# roller-shutter.net
KiCad netlist of a schematic drawn in EAGLE
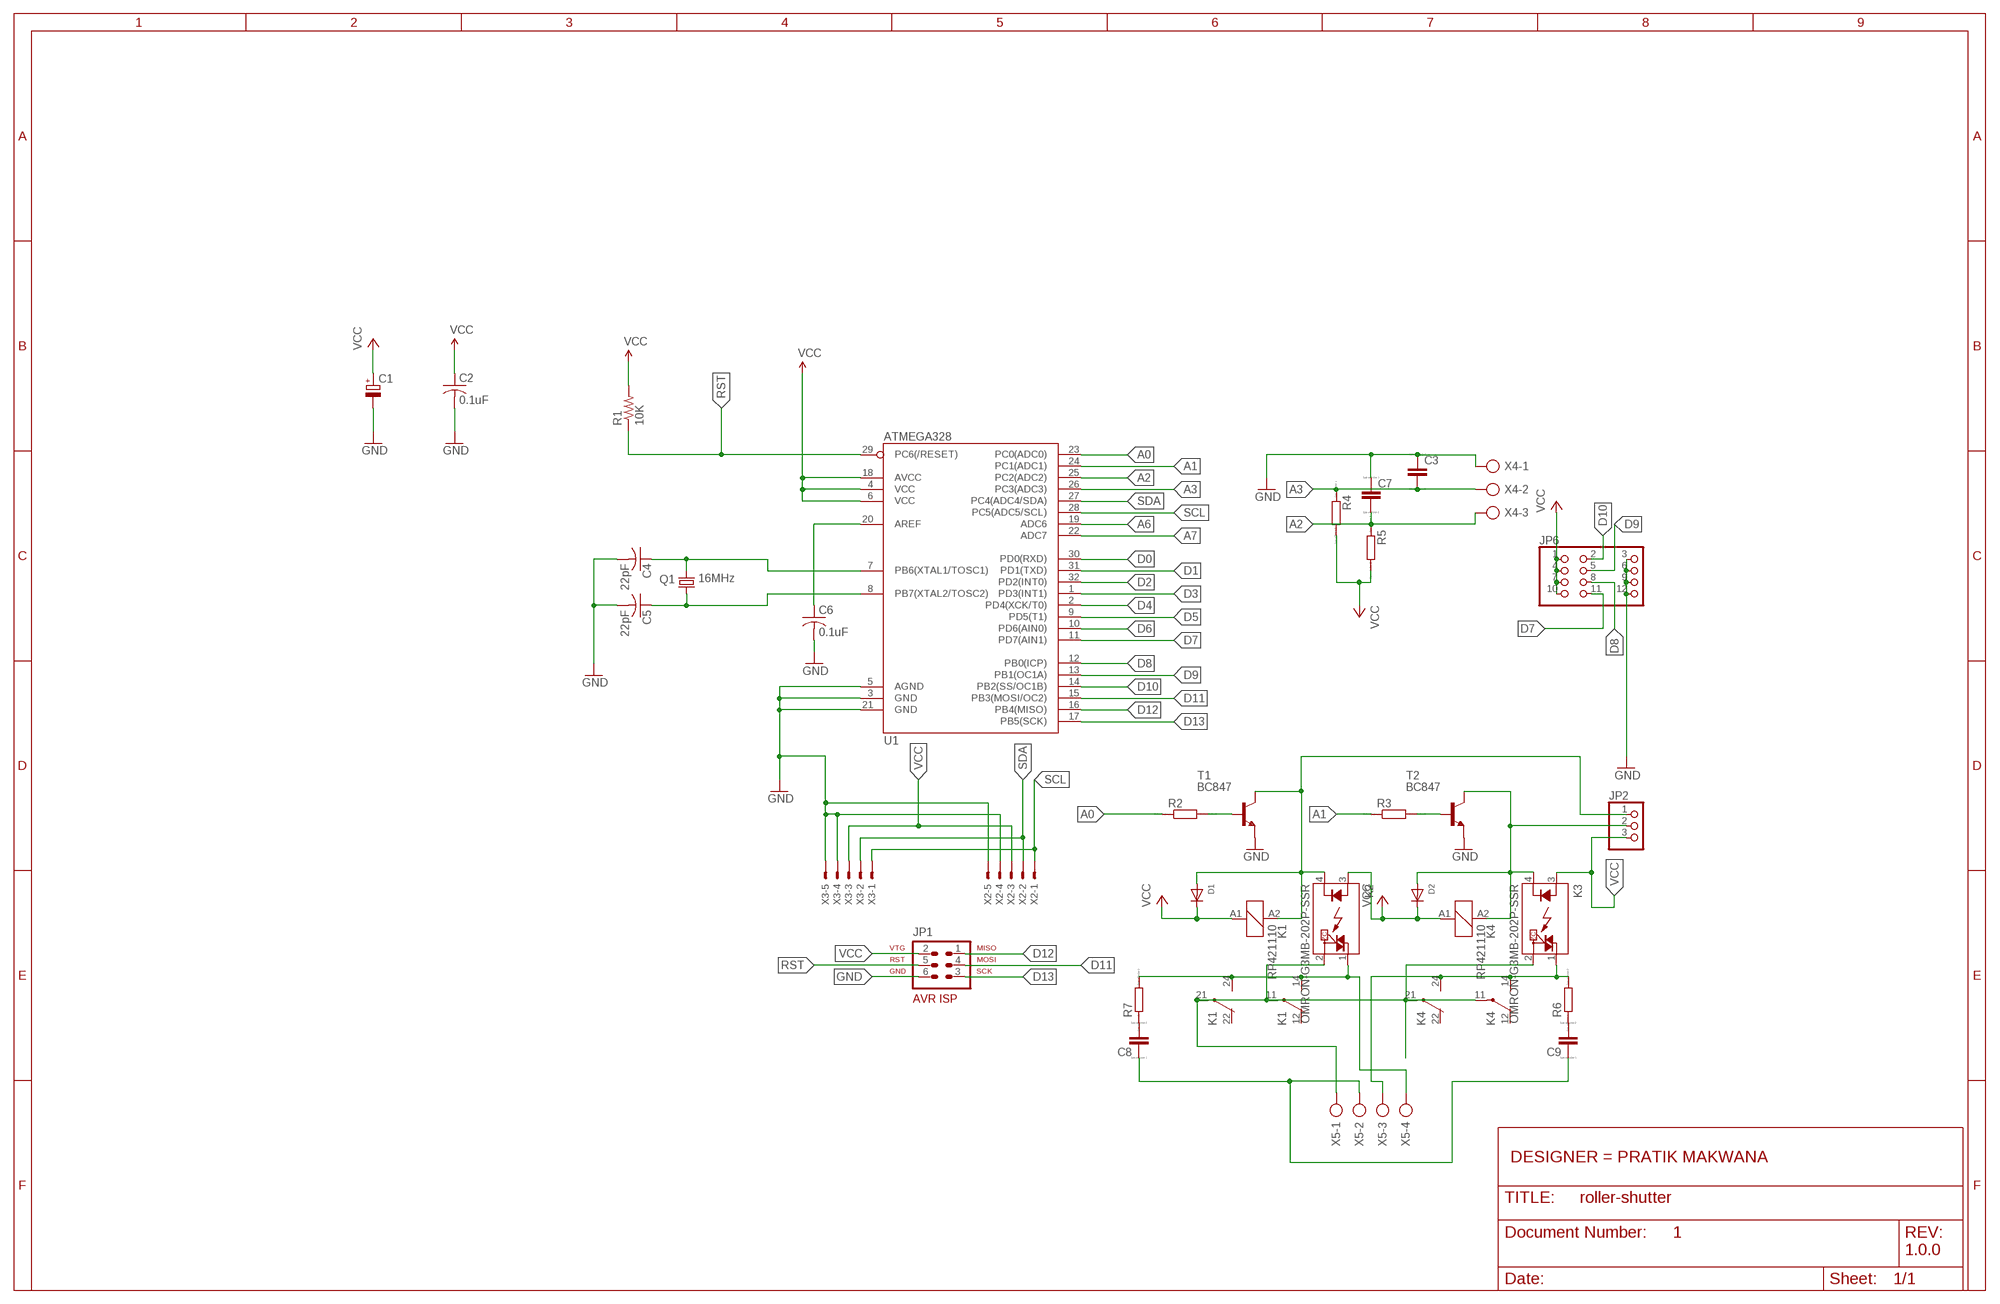
[diagram p0: schematic, sheet 1]

(export (version "E")
  (design (tool "Eeschema 10.0.6"))
  (components
    (comp (ref "C1")
      (value "CPOL-EUSANYO_SMD_C6")
      (footprint "eagle-import:SANYO-OSCON_SMD_C6")
      (libsource (lib "eagle-import") (part "CPOL-EUSANYO_SMD_C6"))
    )
    (comp (ref "C2")
      (value "0.1uF")
      (footprint "eagle-import:C0805")
      (libsource (lib "eagle-import") (part "C-USC0805"))
    )
    (comp (ref "C3") (value "C") (footprint "eagle-import:C0805") (libsource (lib "eagle-import") (part "C")))
    (comp (ref "C4")
      (value "22pF")
      (footprint "eagle-import:C1206")
      (libsource (lib "eagle-import") (part "C-USC1206"))
    )
    (comp (ref "C5")
      (value "22pF")
      (footprint "eagle-import:C1206")
      (libsource (lib "eagle-import") (part "C-USC1206"))
    )
    (comp (ref "C6")
      (value "0.1uF")
      (footprint "eagle-import:C0805")
      (libsource (lib "eagle-import") (part "C-USC0805"))
    )
    (comp (ref "C7") (value "C") (footprint "eagle-import:C0805") (libsource (lib "eagle-import") (part "C")))
    (comp (ref "C8")
      (value "CC1812")
      (footprint "eagle-import:C1812")
      (libsource (lib "eagle-import") (part "CC1812"))
    )
    (comp (ref "C9")
      (value "CC1812")
      (footprint "eagle-import:C1812")
      (libsource (lib "eagle-import") (part "CC1812"))
    )
    (comp (ref "D1")
      (value "DIODE_SOD-123FL")
      (footprint "eagle-import:SOD-123FL")
      (libsource (lib "eagle-import") (part "DIODE_SOD-123FL"))
    )
    (comp (ref "D2")
      (value "DIODE_SOD-123FL")
      (footprint "eagle-import:SOD-123FL")
      (libsource (lib "eagle-import") (part "DIODE_SOD-123FL"))
    )
    (comp (ref "JP1")
      (value "AVR-ISP-6")
      (footprint "eagle-import:AVR-ISP-6")
      (libsource (lib "eagle-import") (part "AVR-ISP-6"))
    )
    (comp (ref "JP2")
      (value "PINHD-1X3")
      (footprint "eagle-import:1X03")
      (libsource (lib "eagle-import") (part "PINHD-1X3"))
    )
    (comp (ref "JP6")
      (value "PINHD-3X4")
      (footprint "eagle-import:3X04")
      (libsource (lib "eagle-import") (part "PINHD-3X4"))
    )
    (comp (ref "K1")
      (value "RP421110")
      (footprint "eagle-import:RP420")
      (fields (field (name "MF") "TYCO ELECTRONICS"))
      (libsource (lib "eagle-import") (part "RP42?1110"))
    )
    (comp (ref "K2")
      (value "OMRON-G3MB-202P-SSR")
      (footprint "eagle-import:OMRON-G3MB-202P-SSR")
      (libsource (lib "eagle-import") (part "OMRON-G3MB-202P-SSR"))
    )
    (comp (ref "K3")
      (value "OMRON-G3MB-202P-SSR")
      (footprint "eagle-import:OMRON-G3MB-202P-SSR")
      (libsource (lib "eagle-import") (part "OMRON-G3MB-202P-SSR"))
    )
    (comp (ref "K4")
      (value "RP421110")
      (footprint "eagle-import:RP420")
      (fields (field (name "MF") "TYCO ELECTRONICS"))
      (libsource (lib "eagle-import") (part "RP42?1110"))
    )
    (comp (ref "Q1")
      (value "16MHz")
      (footprint "eagle-import:HC49_S")
      (libsource (lib "eagle-import") (part "CRYTALHC49S"))
    )
    (comp (ref "R1")
      (value "10K")
      (footprint "eagle-import:R1206")
      (libsource (lib "eagle-import") (part "R-US_R1206"))
    )
    (comp (ref "R2")
      (value "RR1206")
      (footprint "eagle-import:R1206")
      (libsource (lib "eagle-import") (part "RR1206"))
    )
    (comp (ref "R3")
      (value "RR1206")
      (footprint "eagle-import:R1206")
      (libsource (lib "eagle-import") (part "RR1206"))
    )
    (comp (ref "R4")
      (value "RR1206")
      (footprint "eagle-import:R1206")
      (libsource (lib "eagle-import") (part "RR1206"))
    )
    (comp (ref "R5")
      (value "RR1206")
      (footprint "eagle-import:R1206")
      (libsource (lib "eagle-import") (part "RR1206"))
    )
    (comp (ref "R6")
      (value "RR2512")
      (footprint "eagle-import:R2512")
      (libsource (lib "eagle-import") (part "RR2512"))
    )
    (comp (ref "R7")
      (value "RR2512")
      (footprint "eagle-import:R2512")
      (libsource (lib "eagle-import") (part "RR2512"))
    )
    (comp (ref "T1")
      (value "BC847")
      (footprint "eagle-import:SOT23")
      (libsource (lib "eagle-import") (part "BC847"))
    )
    (comp (ref "T2")
      (value "BC847")
      (footprint "eagle-import:SOT23")
      (libsource (lib "eagle-import") (part "BC847"))
    )
    (comp (ref "U1")
      (value "ATMEGA328")
      (footprint "eagle-import:TQFP32-08")
      (libsource (lib "eagle-import") (part "ATMEGA328"))
    )
    (comp (ref "X2")
      (value "JST-XH-05-PIN-LONG-PAD")
      (footprint "eagle-import:JST-XH-05-PACKAGE-LONG-PAD")
      (libsource (lib "eagle-import") (part "JST-XH-05-PIN-LONG-PAD"))
    )
    (comp (ref "X3")
      (value "JST-XH-05-PIN-LONG-PAD")
      (footprint "eagle-import:JST-XH-05-PACKAGE-LONG-PAD")
      (libsource (lib "eagle-import") (part "JST-XH-05-PIN-LONG-PAD"))
    )
    (comp (ref "X4")
      (value "AK500/3")
      (footprint "eagle-import:AK500_3")
      (libsource (lib "eagle-import") (part "AK500/3"))
    )
    (comp (ref "X5")
      (value "AK500/4")
      (footprint "eagle-import:AK500_4")
      (libsource (lib "eagle-import") (part "AK500/4"))
    )
  )
  (nets
    (net (code "1") (name "A0") (class "Default")
      (node (ref "R2") (pin "1") (pinfunction "1_1") (pintype "passive"))
      (node (ref "U1") (pin "23") (pinfunction "PC0(ADC0)_23") (pintype "bidirectional"))
    )
    (net (code "2") (name "A1") (class "Default")
      (node (ref "R3") (pin "1") (pinfunction "1_1") (pintype "passive"))
      (node (ref "U1") (pin "24") (pinfunction "PC1(ADC1)_24") (pintype "bidirectional"))
    )
    (net (code "3") (name "A2") (class "Default")
      (node (ref "C7") (pin "2") (pinfunction "2_2") (pintype "passive"))
      (node (ref "R5") (pin "1") (pinfunction "1_1") (pintype "passive"))
      (node (ref "U1") (pin "25") (pinfunction "PC2(ADC2)_25") (pintype "bidirectional"))
      (node (ref "X4") (pin "3") (pinfunction "KL_3") (pintype "passive"))
    )
    (net (code "4") (name "A3") (class "Default")
      (node (ref "C3") (pin "2") (pinfunction "2_2") (pintype "passive"))
      (node (ref "R4") (pin "1") (pinfunction "1_1") (pintype "passive"))
      (node (ref "U1") (pin "26") (pinfunction "PC3(ADC3)_26") (pintype "bidirectional"))
      (node (ref "X4") (pin "2") (pinfunction "KL_2") (pintype "passive"))
    )
    (net (code "5") (name "A6") (class "Default")
      (node (ref "U1") (pin "19") (pinfunction "ADC6_19") (pintype "bidirectional"))
    )
    (net (code "6") (name "A7") (class "Default")
      (node (ref "U1") (pin "22") (pinfunction "ADC7_22") (pintype "bidirectional"))
    )
    (net (code "7") (name "D0") (class "Default")
      (node (ref "U1") (pin "30") (pinfunction "PD0(RXD)_30") (pintype "bidirectional"))
    )
    (net (code "8") (name "D1") (class "Default")
      (node (ref "U1") (pin "31") (pinfunction "PD1(TXD)_31") (pintype "bidirectional"))
    )
    (net (code "9") (name "D2") (class "Default")
      (node (ref "U1") (pin "32") (pinfunction "PD2(INT0)_32") (pintype "bidirectional"))
    )
    (net (code "10") (name "D3") (class "Default")
      (node (ref "U1") (pin "1") (pinfunction "PD3(INT1)_1") (pintype "bidirectional"))
    )
    (net (code "11") (name "D4") (class "Default")
      (node (ref "U1") (pin "2") (pinfunction "PD4(XCK/T0)_2") (pintype "bidirectional"))
    )
    (net (code "12") (name "D5") (class "Default")
      (node (ref "U1") (pin "9") (pinfunction "PD5(T1)_9") (pintype "bidirectional"))
    )
    (net (code "13") (name "D6") (class "Default")
      (node (ref "U1") (pin "10") (pinfunction "PD6(AIN0)_10") (pintype "bidirectional"))
    )
    (net (code "14") (name "D7") (class "Default")
      (node (ref "JP6") (pin "11") (pinfunction "11_11") (pintype "passive"))
      (node (ref "U1") (pin "11") (pinfunction "PD7(AIN1)_11") (pintype "bidirectional"))
    )
    (net (code "15") (name "D8") (class "Default")
      (node (ref "JP6") (pin "8") (pinfunction "8_8") (pintype "passive"))
      (node (ref "U1") (pin "12") (pinfunction "PB0(ICP)_12") (pintype "bidirectional"))
    )
    (net (code "16") (name "D9") (class "Default")
      (node (ref "JP6") (pin "5") (pinfunction "5_5") (pintype "passive"))
      (node (ref "U1") (pin "13") (pinfunction "PB1(OC1A)_13") (pintype "bidirectional"))
    )
    (net (code "17") (name "D10") (class "Default")
      (node (ref "JP6") (pin "2") (pinfunction "2_2") (pintype "passive"))
      (node (ref "U1") (pin "14") (pinfunction "PB2(SS/OC1B)_14") (pintype "bidirectional"))
    )
    (net (code "18") (name "D11") (class "Default")
      (node (ref "JP1") (pin "4") (pinfunction "4_4") (pintype "passive"))
      (node (ref "U1") (pin "15") (pinfunction "PB3(MOSI/OC2)_15") (pintype "bidirectional"))
    )
    (net (code "19") (name "D12") (class "Default")
      (node (ref "JP1") (pin "1") (pinfunction "1_1") (pintype "passive"))
      (node (ref "U1") (pin "16") (pinfunction "PB4(MISO)_16") (pintype "bidirectional"))
    )
    (net (code "20") (name "D13") (class "Default")
      (node (ref "JP1") (pin "3") (pinfunction "3_3") (pintype "passive"))
      (node (ref "U1") (pin "17") (pinfunction "PB5(SCK)_17") (pintype "bidirectional"))
    )
    (net (code "21") (name "GND") (class "Default")
      (node (ref "C1") (pin "-") (pinfunction "-_-") (pintype "passive"))
      (node (ref "C2") (pin "2") (pinfunction "2_2") (pintype "passive"))
      (node (ref "C3") (pin "1") (pinfunction "1_1") (pintype "passive"))
      (node (ref "C4") (pin "2") (pinfunction "2_2") (pintype "passive"))
      (node (ref "C5") (pin "2") (pinfunction "2_2") (pintype "passive"))
      (node (ref "C6") (pin "2") (pinfunction "2_2") (pintype "passive"))
      (node (ref "C7") (pin "1") (pinfunction "1_1") (pintype "passive"))
      (node (ref "JP1") (pin "6") (pinfunction "6_6") (pintype "passive"))
      (node (ref "JP6") (pin "12") (pinfunction "12_12") (pintype "passive"))
      (node (ref "JP6") (pin "3") (pinfunction "3_3") (pintype "passive"))
      (node (ref "JP6") (pin "6") (pinfunction "6_6") (pintype "passive"))
      (node (ref "JP6") (pin "9") (pinfunction "9_9") (pintype "passive"))
      (node (ref "T1") (pin "2") (pinfunction "E_2") (pintype "passive"))
      (node (ref "T2") (pin "2") (pinfunction "E_2") (pintype "passive"))
      (node (ref "U1") (pin "21") (pinfunction "GND_21") (pintype "bidirectional"))
      (node (ref "U1") (pin "3") (pinfunction "GND_3") (pintype "bidirectional"))
      (node (ref "U1") (pin "5") (pinfunction "AGND_5") (pintype "bidirectional"))
      (node (ref "X2") (pin "4") (pinfunction "S_4") (pintype "passive"))
      (node (ref "X2") (pin "5") (pinfunction "S_5") (pintype "passive"))
      (node (ref "X3") (pin "4") (pinfunction "S_4") (pintype "passive"))
      (node (ref "X3") (pin "5") (pinfunction "S_5") (pintype "passive"))
      (node (ref "X4") (pin "1") (pinfunction "KL_1") (pintype "passive"))
    )
    (net (code "22") (name "Net-(C8-Pad2)") (class "Default")
      (node (ref "C8") (pin "2") (pinfunction "2_2") (pintype "passive"))
      (node (ref "R7") (pin "1") (pinfunction "1_1") (pintype "passive"))
    )
    (net (code "23") (name "Net-(C9-Pad2)") (class "Default")
      (node (ref "C9") (pin "2") (pinfunction "2_2") (pintype "passive"))
      (node (ref "R6") (pin "1") (pinfunction "1_1") (pintype "passive"))
    )
    (net (code "24") (name "Net-(K1A-1)") (class "Default")
      (node (ref "D1") (pin "A") (pinfunction "A_A") (pintype "passive"))
      (node (ref "JP2") (pin "1") (pinfunction "1_1") (pintype "passive"))
      (node (ref "K1") (pin "A2") (pinfunction "1_A2") (pintype "passive"))
      (node (ref "K2") (pin "4") (pinfunction "K_4") (pintype "passive"))
      (node (ref "T1") (pin "3") (pinfunction "C_3") (pintype "passive"))
    )
    (net (code "25") (name "Net-(K1B-P)") (class "Default")
      (node (ref "K1") (pin "11") (pinfunction "P_11") (pintype "passive"))
      (node (ref "K1") (pin "21") (pinfunction "P_21") (pintype "passive"))
      (node (ref "K2") (pin "2") (pinfunction "DS2_2") (pintype "passive"))
      (node (ref "K3") (pin "2") (pinfunction "DS2_2") (pintype "passive"))
      (node (ref "K4") (pin "11") (pinfunction "P_11") (pintype "passive"))
      (node (ref "K4") (pin "21") (pinfunction "P_21") (pintype "passive"))
      (node (ref "X5") (pin "1") (pinfunction "KL_1") (pintype "passive"))
    )
    (net (code "26") (name "Net-(K1B-S)") (class "Default")
      (node (ref "K1") (pin "14") (pinfunction "S_14") (pintype "passive"))
      (node (ref "K1") (pin "24") (pinfunction "S_24") (pintype "passive"))
      (node (ref "K2") (pin "1") (pinfunction "DS1_1") (pintype "passive"))
      (node (ref "R7") (pin "2") (pinfunction "2_2") (pintype "passive"))
      (node (ref "X5") (pin "4") (pinfunction "KL_4") (pintype "passive"))
    )
    (net (code "27") (name "Net-(K3-DS1)") (class "Default")
      (node (ref "K3") (pin "1") (pinfunction "DS1_1") (pintype "passive"))
      (node (ref "K4") (pin "14") (pinfunction "S_14") (pintype "passive"))
      (node (ref "K4") (pin "24") (pinfunction "S_24") (pintype "passive"))
      (node (ref "R6") (pin "2") (pinfunction "2_2") (pintype "passive"))
      (node (ref "X5") (pin "3") (pinfunction "KL_3") (pintype "passive"))
    )
    (net (code "28") (name "Net-(K3-K)") (class "Default")
      (node (ref "D2") (pin "A") (pinfunction "A_A") (pintype "passive"))
      (node (ref "JP2") (pin "2") (pinfunction "2_2") (pintype "passive"))
      (node (ref "K3") (pin "4") (pinfunction "K_4") (pintype "passive"))
      (node (ref "K4") (pin "A2") (pinfunction "1_A2") (pintype "passive"))
      (node (ref "T2") (pin "3") (pinfunction "C_3") (pintype "passive"))
    )
    (net (code "29") (name "Net-(T1-B)") (class "Default")
      (node (ref "R2") (pin "2") (pinfunction "2_2") (pintype "passive"))
      (node (ref "T1") (pin "1") (pinfunction "B_1") (pintype "passive"))
    )
    (net (code "30") (name "Net-(T2-B)") (class "Default")
      (node (ref "R3") (pin "2") (pinfunction "2_2") (pintype "passive"))
      (node (ref "T2") (pin "1") (pinfunction "B_1") (pintype "passive"))
    )
    (net (code "31") (name "Net-(U1-AREF)") (class "Default")
      (node (ref "C6") (pin "1") (pinfunction "1_1") (pintype "passive"))
      (node (ref "U1") (pin "20") (pinfunction "AREF_20") (pintype "bidirectional"))
    )
    (net (code "32") (name "Net-(U1-PB6(XTAL1{slash}TOSC1))") (class "Default")
      (node (ref "C4") (pin "1") (pinfunction "1_1") (pintype "passive"))
      (node (ref "Q1") (pin "2") (pinfunction "2_2") (pintype "passive"))
      (node (ref "U1") (pin "7") (pinfunction "PB6(XTAL1/TOSC1)_7") (pintype "bidirectional"))
    )
    (net (code "33") (name "Net-(U1-PB7(XTAL2{slash}TOSC2))") (class "Default")
      (node (ref "C5") (pin "1") (pinfunction "1_1") (pintype "passive"))
      (node (ref "Q1") (pin "1") (pinfunction "1_1") (pintype "passive"))
      (node (ref "U1") (pin "8") (pinfunction "PB7(XTAL2/TOSC2)_8") (pintype "bidirectional"))
    )
    (net (code "34") (name "Net-(X5B-KL)") (class "Default")
      (node (ref "C8") (pin "1") (pinfunction "1_1") (pintype "passive"))
      (node (ref "C9") (pin "1") (pinfunction "1_1") (pintype "passive"))
      (node (ref "X5") (pin "2") (pinfunction "KL_2") (pintype "passive"))
    )
    (net (code "35") (name "RST") (class "Default")
      (node (ref "JP1") (pin "5") (pinfunction "5_5") (pintype "passive"))
      (node (ref "R1") (pin "1") (pinfunction "1_1") (pintype "passive"))
      (node (ref "U1") (pin "29") (pinfunction "PC6(/RESET)_29") (pintype "bidirectional"))
    )
    (net (code "36") (name "SCL") (class "Default")
      (node (ref "U1") (pin "28") (pinfunction "PC5(ADC5/SCL)_28") (pintype "bidirectional"))
      (node (ref "X2") (pin "1") (pinfunction "S_1") (pintype "passive"))
      (node (ref "X3") (pin "1") (pinfunction "S_1") (pintype "passive"))
    )
    (net (code "37") (name "SDA") (class "Default")
      (node (ref "U1") (pin "27") (pinfunction "PC4(ADC4/SDA)_27") (pintype "bidirectional"))
      (node (ref "X2") (pin "2") (pinfunction "S_2") (pintype "passive"))
      (node (ref "X3") (pin "2") (pinfunction "S_2") (pintype "passive"))
    )
    (net (code "38") (name "VCC") (class "Default")
      (node (ref "C1") (pin "+") (pinfunction "+_+") (pintype "passive"))
      (node (ref "C2") (pin "1") (pinfunction "1_1") (pintype "passive"))
      (node (ref "D1") (pin "C") (pinfunction "C_C") (pintype "passive"))
      (node (ref "D2") (pin "C") (pinfunction "C_C") (pintype "passive"))
      (node (ref "JP1") (pin "2") (pinfunction "2_2") (pintype "passive"))
      (node (ref "JP2") (pin "3") (pinfunction "3_3") (pintype "passive"))
      (node (ref "JP6") (pin "1") (pinfunction "1_1") (pintype "passive"))
      (node (ref "JP6") (pin "10") (pinfunction "10_10") (pintype "passive"))
      (node (ref "JP6") (pin "4") (pinfunction "4_4") (pintype "passive"))
      (node (ref "JP6") (pin "7") (pinfunction "7_7") (pintype "passive"))
      (node (ref "K1") (pin "A1") (pinfunction "2_A1") (pintype "passive"))
      (node (ref "K2") (pin "3") (pinfunction "A_3") (pintype "passive"))
      (node (ref "K3") (pin "3") (pinfunction "A_3") (pintype "passive"))
      (node (ref "K4") (pin "A1") (pinfunction "2_A1") (pintype "passive"))
      (node (ref "R1") (pin "2") (pinfunction "2_2") (pintype "passive"))
      (node (ref "R4") (pin "2") (pinfunction "2_2") (pintype "passive"))
      (node (ref "R5") (pin "2") (pinfunction "2_2") (pintype "passive"))
      (node (ref "U1") (pin "18") (pinfunction "AVCC_18") (pintype "bidirectional"))
      (node (ref "U1") (pin "4") (pinfunction "VCC_4") (pintype "bidirectional"))
      (node (ref "U1") (pin "6") (pinfunction "VCC_6") (pintype "bidirectional"))
      (node (ref "X2") (pin "3") (pinfunction "S_3") (pintype "passive"))
      (node (ref "X3") (pin "3") (pinfunction "S_3") (pintype "passive"))
    )
    (net (code "39") (name "unconnected-(K1B-O-Pad12)") (class "Default")
      (node (ref "K1") (pin "12") (pinfunction "O_12") (pintype "passive"))
    )
    (net (code "40") (name "unconnected-(K1C-O-Pad22)") (class "Default")
      (node (ref "K1") (pin "22") (pinfunction "O_22") (pintype "passive"))
    )
    (net (code "41") (name "unconnected-(K4B-O-Pad12)") (class "Default")
      (node (ref "K4") (pin "12") (pinfunction "O_12") (pintype "passive"))
    )
    (net (code "42") (name "unconnected-(K4C-O-Pad22)") (class "Default")
      (node (ref "K4") (pin "22") (pinfunction "O_22") (pintype "passive"))
    )
  )
)
